# 4-Memorie.net
KiCad netlist of a schematic drawn in Altium Designer
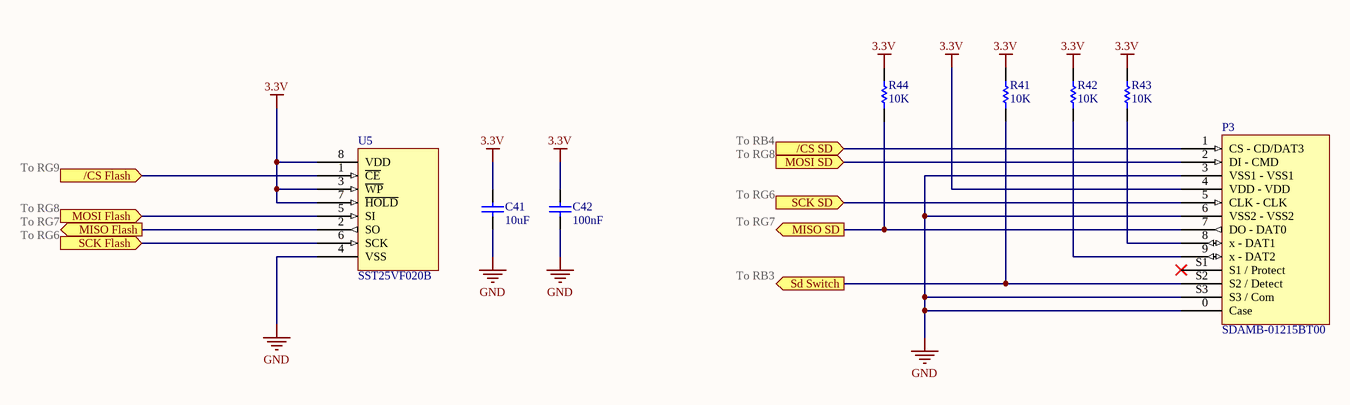
[diagram p0: 4-Memorie.SchDoc]

(export (version "E")
  (design (tool "Eeschema 10.0.6"))
  (components
    (comp (ref "C41")
      (value "10uF")
      (footprint "capa 1206")
      (description "Capacitor")
      (libsource (lib "Miscellaneous Devices") (part "Cap"))
    )
    (comp (ref "C42")
      (value "100nF")
      (footprint "capa 1206")
      (description "Capacitor")
      (libsource (lib "Miscellaneous Devices") (part "Cap"))
    )
    (comp (ref "P3") (value "SDAMB-01215BT00") (libsource (lib "0x2a002a") (part "SDAMB-01215BT00")))
    (comp (ref "R41")
      (value "10K")
      (footprint "RES 1206")
      (description "Resistor")
      (libsource (lib "Miscellaneous Devices") (part "Res1"))
    )
    (comp (ref "R42")
      (value "10K")
      (footprint "RES 1206")
      (description "Resistor")
      (libsource (lib "Miscellaneous Devices") (part "Res1"))
    )
    (comp (ref "R43")
      (value "10K")
      (footprint "RES 1206")
      (description "Resistor")
      (libsource (lib "Miscellaneous Devices") (part "Res1"))
    )
    (comp (ref "R44")
      (value "10K")
      (footprint "RES 1206")
      (description "Resistor")
      (libsource (lib "Miscellaneous Devices") (part "Res1"))
    )
    (comp (ref "U5")
      (value "SST25VF020B")
      (footprint "SST25VF020B")
      (libsource (lib "0x2a002a") (part "SST25VF020B"))
    )
  )
  (nets
    (net (code "1") (name "/MISO Flash") (class "Default")
      (node (ref "U5") (pin "2") (pinfunction "SO_2") (pintype "output"))
    )
    (net (code "2") (name "/MISO SD") (class "Default")
      (node (ref "P3") (pin "7") (pinfunction "DO_-_DAT0_7") (pintype "output"))
      (node (ref "R44") (pin "1") (pinfunction "1_1") (pintype "passive"))
    )
    (net (code "3") (name "/MOSI Flash") (class "Default")
      (node (ref "U5") (pin "5") (pinfunction "SI_5") (pintype "input"))
    )
    (net (code "4") (name "/MOSI SD") (class "Default")
      (node (ref "P3") (pin "2") (pinfunction "DI_-_CMD_2") (pintype "input"))
    )
    (net (code "5") (name "/SCK Flash") (class "Default")
      (node (ref "U5") (pin "6") (pinfunction "SCK_6") (pintype "input"))
    )
    (net (code "6") (name "/SCK SD") (class "Default")
      (node (ref "P3") (pin "5") (pinfunction "CLK_-_CLK_5") (pintype "input"))
    )
    (net (code "7") (name "/Sd Switch") (class "Default")
      (node (ref "P3") (pin "S2") (pinfunction "S2_/_Detect_S2") (pintype "passive"))
      (node (ref "R41") (pin "1") (pinfunction "1_1") (pintype "passive"))
    )
    (net (code "8") (name "/{slash}CS Flash") (class "Default")
      (node (ref "U5") (pin "1") (pinfunction "~{CE}_1") (pintype "input"))
    )
    (net (code "9") (name "/{slash}CS SD") (class "Default")
      (node (ref "P3") (pin "1") (pinfunction "CS_-_CD/DAT3_1") (pintype "input"))
    )
    (net (code "10") (name "3.3V") (class "Default")
      (node (ref "C41") (pin "1") (pinfunction "1_1") (pintype "passive"))
      (node (ref "C42") (pin "1") (pinfunction "1_1") (pintype "passive"))
      (node (ref "P3") (pin "4") (pinfunction "VDD_-_VDD_4") (pintype "power_in"))
      (node (ref "R41") (pin "2") (pinfunction "2_2") (pintype "passive"))
      (node (ref "R42") (pin "2") (pinfunction "2_2") (pintype "passive"))
      (node (ref "R43") (pin "2") (pinfunction "2_2") (pintype "passive"))
      (node (ref "R44") (pin "2") (pinfunction "2_2") (pintype "passive"))
      (node (ref "U5") (pin "3") (pinfunction "~{WP}_3") (pintype "input"))
      (node (ref "U5") (pin "7") (pinfunction "~{HOLD}_7") (pintype "input"))
      (node (ref "U5") (pin "8") (pinfunction "VDD_8") (pintype "power_in"))
    )
    (net (code "11") (name "GND") (class "Default")
      (node (ref "C41") (pin "2") (pinfunction "2_2") (pintype "passive"))
      (node (ref "C42") (pin "2") (pinfunction "2_2") (pintype "passive"))
      (node (ref "P3") (pin "0") (pinfunction "Case_0") (pintype "passive"))
      (node (ref "P3") (pin "3") (pinfunction "VSS1_-_VSS1_3") (pintype "power_in"))
      (node (ref "P3") (pin "6") (pinfunction "VSS2_-_VSS2_6") (pintype "power_in"))
      (node (ref "P3") (pin "S3") (pinfunction "S3_/_Com_S3") (pintype "passive"))
      (node (ref "U5") (pin "4") (pinfunction "VSS_4") (pintype "power_in"))
    )
    (net (code "12") (name "Net-(P3-x_-_DAT1)") (class "Default")
      (node (ref "P3") (pin "8") (pinfunction "x_-_DAT1_8") (pintype "bidirectional"))
      (node (ref "R43") (pin "1") (pinfunction "1_1") (pintype "passive"))
    )
    (net (code "13") (name "Net-(P3-x_-_DAT2)") (class "Default")
      (node (ref "P3") (pin "9") (pinfunction "x_-_DAT2_9") (pintype "bidirectional"))
      (node (ref "R42") (pin "1") (pinfunction "1_1") (pintype "passive"))
    )
    (net (code "14") (name "unconnected-(P3-S1_{slash}_Protect-PadS1)") (class "Default")
      (node (ref "P3") (pin "S1") (pinfunction "S1_/_Protect_S1") (pintype "passive+no_connect"))
    )
  )
)
